# LED_Inducator.net
KiCad netlist of a schematic drawn in Altium Designer
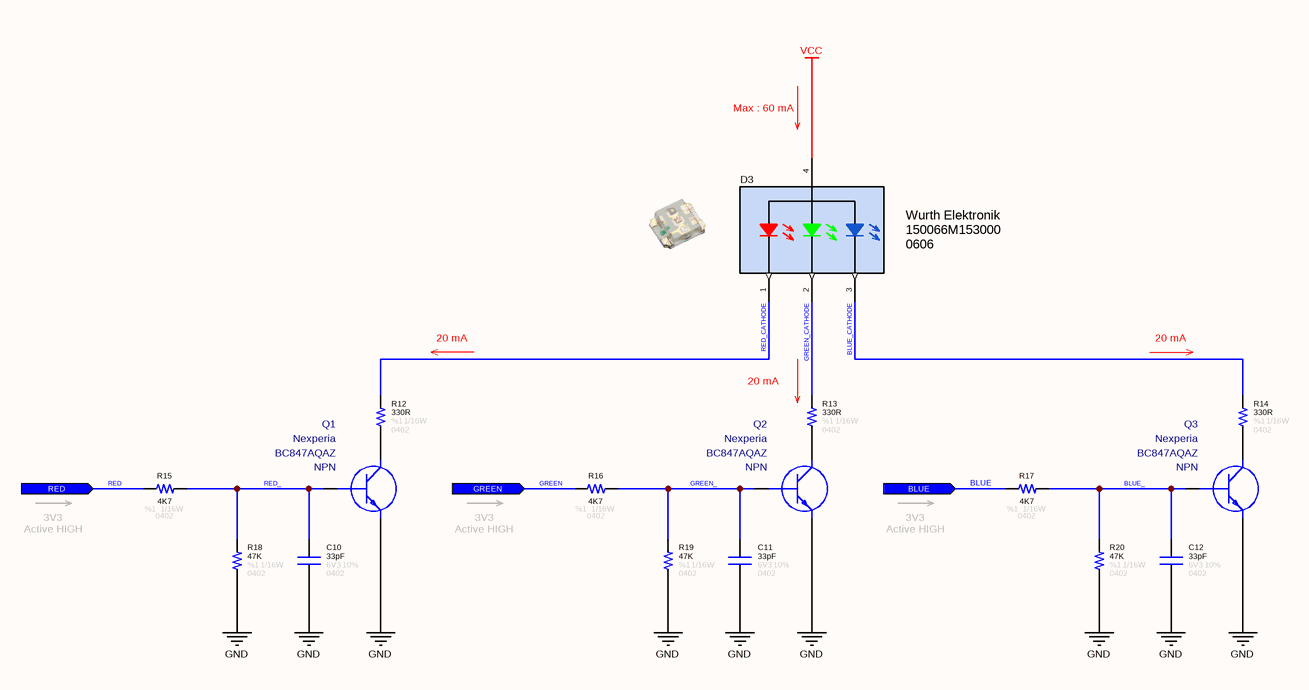
[diagram p0: LED Inducator.SchDoc]

(export (version "E")
  (design (tool "Eeschema 10.0.6"))
  (components
    (comp (ref "C10")
      (value "33pF")
      (footprint "CAPACITOR_0402")
      (description "Capacitor - 33pF [0402] (Ceramic)")
      (fields
        (field (name "MANUFACTURER PART NUMBER") "C0402C330J9RACAUTO")
        (field (name "TOLERANCE") "10%")
        (field (name "CASE") "0402")
        (field (name "VOLTAGE") "6V3")
      )
      (libsource (lib "P101DA_Library") (part "Capacitor - 33pF [0402-6V3]"))
    )
    (comp (ref "C11")
      (value "33pF")
      (footprint "CAPACITOR_0402")
      (description "Capacitor - 33pF [0402] (Ceramic)")
      (fields
        (field (name "MANUFACTURER PART NUMBER") "C0402C330J9RACAUTO")
        (field (name "TOLERANCE") "10%")
        (field (name "CASE") "0402")
        (field (name "VOLTAGE") "6V3")
      )
      (libsource (lib "P101DA_Library") (part "Capacitor - 33pF [0402-6V3]"))
    )
    (comp (ref "C12")
      (value "33pF")
      (footprint "CAPACITOR_0402")
      (description "Capacitor - 33pF [0402] (Ceramic)")
      (fields
        (field (name "MANUFACTURER PART NUMBER") "C0402C330J9RACAUTO")
        (field (name "TOLERANCE") "10%")
        (field (name "CASE") "0402")
        (field (name "VOLTAGE") "6V3")
      )
      (libsource (lib "P101DA_Library") (part "Capacitor - 33pF [0402-6V3]"))
    )
    (comp (ref "D3")
      (value "150066M153000")
      (footprint "Wurth_0606")
      (description "LED RGB DIFFUSED SMD")
      (fields
        (field (name "MANUFACTURER NAME") "Wurth Elektronik")
        (field (name "MANUFACTURER PART NUMBER") "150066M153000")
        (field (name "CASE") "0606")
      )
      (libsource (lib "P101DA_Library") (part "Diode - LED-RGB"))
    )
    (comp (ref "Q1")
      (value "BC847AQAZ")
      (footprint "SOT1215")
      (description "Bipolar NPN Transistors")
      (fields
        (field (name "MANUFACTURER NAME") "Nexperia")
        (field (name "MANUFACTURER PART NUMBER") "BC847AQAZ")
        (field (name "POLARITY") "NPN")
      )
      (libsource (lib "P101DA_Library") (part "Transistor - BC847"))
    )
    (comp (ref "Q2")
      (value "BC847AQAZ")
      (footprint "SOT1215")
      (description "Bipolar NPN Transistors")
      (fields
        (field (name "MANUFACTURER NAME") "Nexperia")
        (field (name "MANUFACTURER PART NUMBER") "BC847AQAZ")
        (field (name "POLARITY") "NPN")
      )
      (libsource (lib "P101DA_Library") (part "Transistor - BC847"))
    )
    (comp (ref "Q3")
      (value "BC847AQAZ")
      (footprint "SOT1215")
      (description "Bipolar NPN Transistors")
      (fields
        (field (name "MANUFACTURER NAME") "Nexperia")
        (field (name "MANUFACTURER PART NUMBER") "BC847AQAZ")
        (field (name "POLARITY") "NPN")
      )
      (libsource (lib "P101DA_Library") (part "Transistor - BC847"))
    )
    (comp (ref "R12")
      (value "330R")
      (footprint "RESISTOR_0402")
      (description "Thick Film Resistors - SMD 1/16 W 330 Ohm 1%")
      (fields
        (field (name "MANUFACTURER PART NUMBER") "CRCW0402330RFKED")
        (field (name "CASE") "0402")
        (field (name "TOLERANCE") "%1")
        (field (name "POWER") "1/16W")
        (field (name "Comment") "330R - 0402 - %1 - 1/16W")
      )
      (libsource (lib "P101DA_Library") (part "Resistor - 330R [0402]"))
    )
    (comp (ref "R13")
      (value "330R")
      (footprint "RESISTOR_0402")
      (description "Thick Film Resistors - SMD 1/16 W 330 Ohm 1%")
      (fields
        (field (name "MANUFACTURER PART NUMBER") "CRCW0402330RFKED")
        (field (name "CASE") "0402")
        (field (name "TOLERANCE") "%1")
        (field (name "POWER") "1/16W")
        (field (name "Comment") "330R - 0402 - %1 - 1/16W")
      )
      (libsource (lib "P101DA_Library") (part "Resistor - 330R [0402]"))
    )
    (comp (ref "R14")
      (value "330R")
      (footprint "RESISTOR_0402")
      (description "Thick Film Resistors - SMD 1/16 W 330 Ohm 1%")
      (fields
        (field (name "MANUFACTURER PART NUMBER") "CRCW0402330RFKED")
        (field (name "CASE") "0402")
        (field (name "TOLERANCE") "%1")
        (field (name "POWER") "1/16W")
        (field (name "Comment") "330R - 0402 - %1 - 1/16W")
      )
      (libsource (lib "P101DA_Library") (part "Resistor - 330R [0402]"))
    )
    (comp (ref "R15")
      (value "4K7")
      (footprint "RESISTOR_0402")
      (description "Thick Film Resistors - SMD 1/16 W 4.7 KOhm 1%")
      (fields
        (field (name "MANUFACTURER PART NUMBER") "CRCW04024K70FKED")
        (field (name "TOLERANCE") "%1")
        (field (name "CASE") "0402")
        (field (name "POWER") "1/16W")
        (field (name "Comment") "4K7 - 0402 - %1 - 1/16W")
      )
      (libsource (lib "P101DA_Library") (part "Resistor - 4K7 [0402]"))
    )
    (comp (ref "R16")
      (value "4K7")
      (footprint "RESISTOR_0402")
      (description "Thick Film Resistors - SMD 1/16 W 4.7 KOhm 1%")
      (fields
        (field (name "MANUFACTURER PART NUMBER") "CRCW04024K70FKED")
        (field (name "TOLERANCE") "%1")
        (field (name "CASE") "0402")
        (field (name "POWER") "1/16W")
        (field (name "Comment") "4K7 - 0402 - %1 - 1/16W")
      )
      (libsource (lib "P101DA_Library") (part "Resistor - 4K7 [0402]"))
    )
    (comp (ref "R17")
      (value "4K7")
      (footprint "RESISTOR_0402")
      (description "Thick Film Resistors - SMD 1/16 W 4.7 KOhm 1%")
      (fields
        (field (name "MANUFACTURER PART NUMBER") "CRCW04024K70FKED")
        (field (name "TOLERANCE") "%1")
        (field (name "CASE") "0402")
        (field (name "POWER") "1/16W")
        (field (name "Comment") "4K7 - 0402 - %1 - 1/16W")
      )
      (libsource (lib "P101DA_Library") (part "Resistor - 4K7 [0402]"))
    )
    (comp (ref "R18")
      (value "47K")
      (footprint "RESISTOR_0402")
      (description "Thick Film Resistors - SMD 1/16 W 47 KOhm 1%")
      (fields
        (field (name "MANUFACTURER PART NUMBER") "CRCW040247K0FKED")
        (field (name "TOLERANCE") "%1")
        (field (name "CASE") "0402")
        (field (name "POWER") "1/16W")
        (field (name "Comment") "47K - 0402 - %1 - 1/16W")
      )
      (libsource (lib "P101DA_Library") (part "Resistor - 47K [0402]"))
    )
    (comp (ref "R19")
      (value "47K")
      (footprint "RESISTOR_0402")
      (description "Thick Film Resistors - SMD 1/16 W 47 KOhm 1%")
      (fields
        (field (name "MANUFACTURER PART NUMBER") "CRCW040247K0FKED")
        (field (name "TOLERANCE") "%1")
        (field (name "CASE") "0402")
        (field (name "POWER") "1/16W")
        (field (name "Comment") "47K - 0402 - %1 - 1/16W")
      )
      (libsource (lib "P101DA_Library") (part "Resistor - 47K [0402]"))
    )
    (comp (ref "R20")
      (value "47K")
      (footprint "RESISTOR_0402")
      (description "Thick Film Resistors - SMD 1/16 W 47 KOhm 1%")
      (fields
        (field (name "MANUFACTURER PART NUMBER") "CRCW040247K0FKED")
        (field (name "TOLERANCE") "%1")
        (field (name "CASE") "0402")
        (field (name "POWER") "1/16W")
        (field (name "Comment") "47K - 0402 - %1 - 1/16W")
      )
      (libsource (lib "P101DA_Library") (part "Resistor - 47K [0402]"))
    )
  )
  (nets
    (net (code "1") (name "/BLUE") (class "Default")
      (node (ref "R17") (pin "2") (pinfunction "2_2") (pintype "passive"))
    )
    (net (code "2") (name "/BLUE_") (class "Default")
      (node (ref "C12") (pin "2") (pinfunction "2_2") (pintype "passive"))
      (node (ref "Q3") (pin "1") (pinfunction "B_1") (pintype "passive"))
      (node (ref "R17") (pin "1") (pinfunction "1_1") (pintype "passive"))
      (node (ref "R20") (pin "2") (pinfunction "2_2") (pintype "passive"))
    )
    (net (code "3") (name "/BLUE_CATHODE") (class "Default")
      (node (ref "D3") (pin "3") (pinfunction "3_3") (pintype "output"))
      (node (ref "R14") (pin "2") (pinfunction "2_2") (pintype "passive"))
    )
    (net (code "4") (name "/GREEN") (class "Default")
      (node (ref "R16") (pin "2") (pinfunction "2_2") (pintype "passive"))
    )
    (net (code "5") (name "/GREEN_") (class "Default")
      (node (ref "C11") (pin "2") (pinfunction "2_2") (pintype "passive"))
      (node (ref "Q2") (pin "1") (pinfunction "B_1") (pintype "passive"))
      (node (ref "R16") (pin "1") (pinfunction "1_1") (pintype "passive"))
      (node (ref "R19") (pin "2") (pinfunction "2_2") (pintype "passive"))
    )
    (net (code "6") (name "/GREEN_CATHODE") (class "Default")
      (node (ref "D3") (pin "2") (pinfunction "2_2") (pintype "output"))
      (node (ref "R13") (pin "2") (pinfunction "2_2") (pintype "passive"))
    )
    (net (code "7") (name "/RED") (class "Default")
      (node (ref "R15") (pin "2") (pinfunction "2_2") (pintype "passive"))
    )
    (net (code "8") (name "/RED_") (class "Default")
      (node (ref "C10") (pin "2") (pinfunction "2_2") (pintype "passive"))
      (node (ref "Q1") (pin "1") (pinfunction "B_1") (pintype "passive"))
      (node (ref "R15") (pin "1") (pinfunction "1_1") (pintype "passive"))
      (node (ref "R18") (pin "2") (pinfunction "2_2") (pintype "passive"))
    )
    (net (code "9") (name "/RED_CATHODE") (class "Default")
      (node (ref "D3") (pin "1") (pinfunction "1_1") (pintype "output"))
      (node (ref "R12") (pin "2") (pinfunction "2_2") (pintype "passive"))
    )
    (net (code "10") (name "GND") (class "Default")
      (node (ref "C10") (pin "1") (pinfunction "1_1") (pintype "passive"))
      (node (ref "C11") (pin "1") (pinfunction "1_1") (pintype "passive"))
      (node (ref "C12") (pin "1") (pinfunction "1_1") (pintype "passive"))
      (node (ref "Q1") (pin "2") (pinfunction "E_2") (pintype "passive"))
      (node (ref "Q2") (pin "2") (pinfunction "E_2") (pintype "passive"))
      (node (ref "Q3") (pin "2") (pinfunction "E_2") (pintype "passive"))
      (node (ref "R18") (pin "1") (pinfunction "1_1") (pintype "passive"))
      (node (ref "R19") (pin "1") (pinfunction "1_1") (pintype "passive"))
      (node (ref "R20") (pin "1") (pinfunction "1_1") (pintype "passive"))
    )
    (net (code "11") (name "Net-(Q1-C)") (class "Default")
      (node (ref "Q1") (pin "3") (pinfunction "C_3") (pintype "passive"))
      (node (ref "R12") (pin "1") (pinfunction "1_1") (pintype "passive"))
    )
    (net (code "12") (name "Net-(Q2-C)") (class "Default")
      (node (ref "Q2") (pin "3") (pinfunction "C_3") (pintype "passive"))
      (node (ref "R13") (pin "1") (pinfunction "1_1") (pintype "passive"))
    )
    (net (code "13") (name "Net-(Q3-C)") (class "Default")
      (node (ref "Q3") (pin "3") (pinfunction "C_3") (pintype "passive"))
      (node (ref "R14") (pin "1") (pinfunction "1_1") (pintype "passive"))
    )
    (net (code "14") (name "VCC") (class "Default")
      (node (ref "D3") (pin "4") (pinfunction "4_4") (pintype "power_in"))
    )
  )
)
